# PandMshem.net
KiCad netlist of a schematic drawn in Altium Designer
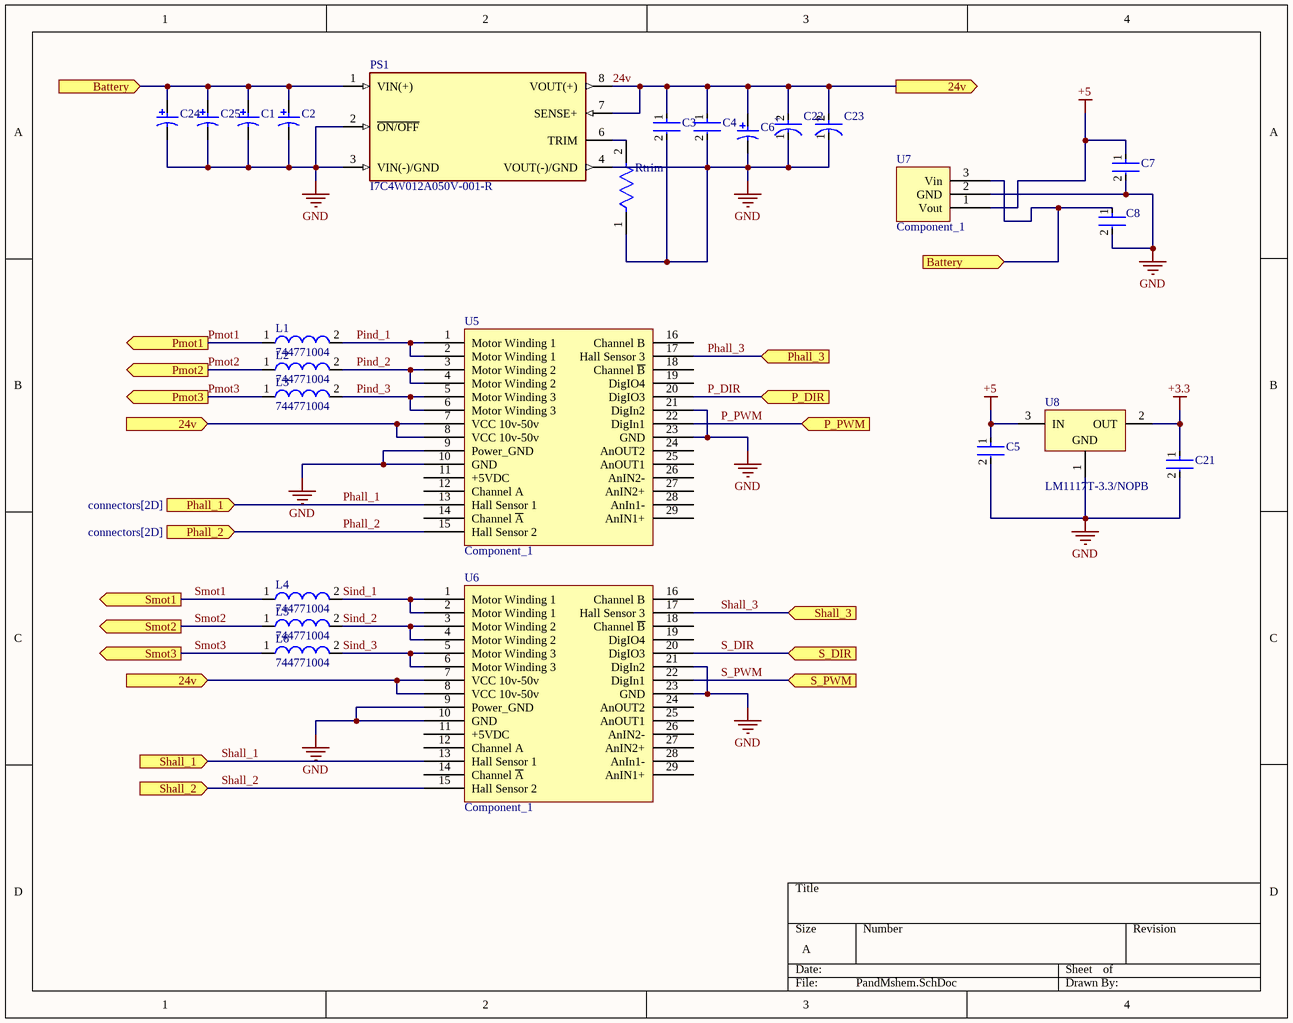
[diagram p0: PandMshem.SchDoc]

(export (version "E")
  (design (tool "Eeschema 10.0.6"))
  (components
    (comp (ref "C1")
      (value "ECA1HM101")
      (footprint "CAPPR65-350-1150X800X1250")
      (description "Aluminum Electrolytic Capacitor, 100 uF, +/- 20%, 50 V, -40 to 85 degC, 2-Pin THD, RoHS, Bulk")
      (fields (field (name "MANUFACTURER") "Panasonic") (field (name "VOLTAGE") "50V"))
      (libsource (lib "Altium Content Vault") (part "CAP-P-2"))
    )
    (comp (ref "C2")
      (value "ECA1HM220")
      (footprint "CAPPR55-200-1100X500X1200")
      (description "Aluminum Electrolytic Capacitor, 22 uF, +/- 20%, 50 V, -40 to 85 degC, 2-Pin THD, RoHS, Bulk")
      (fields (field (name "VOLTAGE") "50V") (field (name "MANUFACTURER") "Panasonic"))
      (libsource (lib "Altium Content Vault") (part "CAP-P-2"))
    )
    (comp (ref "C3")
      (value "08055C105KAT2A")
      (footprint "FP-0805-L_2_01_0_2-W_1_25-MFG")
      (description "General Purpose Ceramic Capacitor, 0805, 1uF, 10%, X7R, 15%, 50V")
      (fields (field (name "TOLERANCE") "10%") (field (name "VOLTAGE") "50V"))
      (libsource (lib "Altium Content Vault") (part "b4654b650e69147ec39a6b967a45e02"))
    )
    (comp (ref "C4")
      (value "C3225X7S1H106M250AB")
      (footprint "FP-C3225-250-0_4-IPC_C")
      (description "Multilayer Ceramic Capacitors 10uF ±20% 50V X7S SMD 1210")
      (fields (field (name "VOLTAGE") "50V") (field (name "TOLERANCE") "20%"))
      (libsource (lib "Altium Content Vault") (part "02cd4be3c70576c341d710602a673aa"))
    )
    (comp (ref "C5")
      (value "C3225X7S1H106M250AB")
      (footprint "FP-C3225-250-0_4-IPC_C")
      (description "Multilayer Ceramic Capacitors 10uF ±20% 50V X7S SMD 1210")
      (fields (field (name "VOLTAGE") "50V") (field (name "TOLERANCE") "20%"))
      (libsource (lib "Altium Content Vault") (part "02cd4be3c70576c341d710602a673aa"))
    )
    (comp (ref "C6")
      (value "ECA1HM101")
      (footprint "CAPPR65-350-1150X800X1250")
      (description "Aluminum Electrolytic Capacitor, 100 uF, +/- 20%, 50 V, -40 to 85 degC, 2-Pin THD, RoHS, Bulk")
      (fields (field (name "MANUFACTURER") "Panasonic") (field (name "VOLTAGE") "50V"))
      (libsource (lib "Altium Content Vault") (part "CAP-P-2"))
    )
    (comp (ref "C7")
      (value "GRM21BR61E226ME44L")
      (footprint "FP-GRM21B-0_2-e0_2_0_7-IPC_B")
      (description "Chip Multilayer Ceramic Capacitors for General Purpose, 0805, 22uF, X5R, 15%, 20%, 25V")
      (fields (field (name "TOLERANCE") "20%") (field (name "VOLTAGE") "25V"))
      (libsource (lib "Altium Content Vault") (part "b4654b650e69147ec39a6b967a45e02"))
    )
    (comp (ref "C8")
      (value "C3225X7S1H106M250AB")
      (footprint "FP-C3225-250-0_4-IPC_C")
      (description "Multilayer Ceramic Capacitors 10uF ±20% 50V X7S SMD 1210")
      (fields (field (name "VOLTAGE") "50V") (field (name "TOLERANCE") "20%"))
      (libsource (lib "Altium Content Vault") (part "02cd4be3c70576c341d710602a673aa"))
    )
    (comp (ref "C21")
      (value "GRM21BR61E226ME44L")
      (footprint "FP-GRM21B-0_2-e0_2_0_7-IPC_B")
      (description "Chip Multilayer Ceramic Capacitors for General Purpose, 0805, 22uF, X5R, 15%, 20%, 25V")
      (fields (field (name "TOLERANCE") "20%") (field (name "VOLTAGE") "25V"))
      (libsource (lib "Altium Content Vault") (part "b4654b650e69147ec39a6b967a45e02"))
    )
    (comp (ref "C22")
      (value "EEUFM1V331B")
      (footprint "FP-RAD-TH-D_10_0_5-L_16_1-MFG")
      (description "Aluminum Electrolytic Capacitors (Radial Lead Type) 330uF ±20% 35V")
      (fields (field (name "TOLERANCE") "20%"))
      (libsource (lib "Altium Content Vault") (part "a00bbbee19879c290e62620ae7e47b1"))
    )
    (comp (ref "C23")
      (value "EEUFM1V331B")
      (footprint "FP-RAD-TH-D_10_0_5-L_16_1-MFG")
      (description "Aluminum Electrolytic Capacitors (Radial Lead Type) 330uF ±20% 35V")
      (fields (field (name "TOLERANCE") "20%"))
      (libsource (lib "Altium Content Vault") (part "a00bbbee19879c290e62620ae7e47b1"))
    )
    (comp (ref "C24")
      (value "ECA1HM101")
      (footprint "CAPPR65-350-1150X800X1250")
      (description "Aluminum Electrolytic Capacitor, 100 uF, +/- 20%, 50 V, -40 to 85 degC, 2-Pin THD, RoHS, Bulk")
      (fields (field (name "MANUFACTURER") "Panasonic") (field (name "VOLTAGE") "50V"))
      (libsource (lib "Altium Content Vault") (part "CAP-P-2"))
    )
    (comp (ref "C25")
      (value "ECA1HM101")
      (footprint "CAPPR65-350-1150X800X1250")
      (description "Aluminum Electrolytic Capacitor, 100 uF, +/- 20%, 50 V, -40 to 85 degC, 2-Pin THD, RoHS, Bulk")
      (fields (field (name "MANUFACTURER") "Panasonic") (field (name "VOLTAGE") "50V"))
      (libsource (lib "Altium Content Vault") (part "CAP-P-2"))
    )
    (comp (ref "L1")
      (value "744771004")
      (footprint "WE-PD-L")
      (description "SMD-Shielded Power Inductor WE-PD, L = 4.70 µH")
      (libsource (lib "Altium Content Vault") (part "PAS-IND-INDUCTOR-2"))
    )
    (comp (ref "L2")
      (value "744771004")
      (footprint "WE-PD-L")
      (description "SMD-Shielded Power Inductor WE-PD, L = 4.70 µH")
      (libsource (lib "Altium Content Vault") (part "PAS-IND-INDUCTOR-2"))
    )
    (comp (ref "L3")
      (value "744771004")
      (footprint "WE-PD-L")
      (description "SMD-Shielded Power Inductor WE-PD, L = 4.70 µH")
      (libsource (lib "Altium Content Vault") (part "PAS-IND-INDUCTOR-2"))
    )
    (comp (ref "L4")
      (value "744771004")
      (footprint "WE-PD-L")
      (description "SMD-Shielded Power Inductor WE-PD, L = 4.70 µH")
      (libsource (lib "Altium Content Vault") (part "PAS-IND-INDUCTOR-2"))
    )
    (comp (ref "L5")
      (value "744771004")
      (footprint "WE-PD-L")
      (description "SMD-Shielded Power Inductor WE-PD, L = 4.70 µH")
      (libsource (lib "Altium Content Vault") (part "PAS-IND-INDUCTOR-2"))
    )
    (comp (ref "L6")
      (value "744771004")
      (footprint "WE-PD-L")
      (description "SMD-Shielded Power Inductor WE-PD, L = 4.70 µH")
      (libsource (lib "Altium Content Vault") (part "PAS-IND-INDUCTOR-2"))
    )
    (comp (ref "PS1")
      (value "I7C4W012A050V-001-R")
      (footprint "CONV_I7C4W012A050V-001-R")
      (description "Non-Isolated PoL Module DC DC Converter 1 Output 5 ~ 28V - - - 12.5A 9V - 53V Input")
      (fields (field (name "MF") "TDK-Lambda Americas Inc"))
      (libsource (lib "I7C4W012A050V-001-R") (part "I7C4W012A050V-001-R"))
    )
    (comp (ref "Rtrim")
      (value "CRCW0805560KFKEA")
      (footprint "FP-CRCW0805-e3-IPC_A")
      (description "RES Thick Film, 560kΩ, 1%, 0.125W, 100ppm/°C, 0805")
      (fields (field (name "TOLERANCE") "1%"))
      (libsource (lib "Altium Content Vault") (part "1029c3af85768c4190bb7ad29bc67b5"))
    )
    (comp (ref "U5")
      (value "Component_1")
      (footprint "Motor_Driver")
      (libsource (lib "MotorDriverSchem") (part "Component_1"))
    )
    (comp (ref "U6")
      (value "Component_1")
      (footprint "Motor_Driver")
      (libsource (lib "MotorDriverSchem") (part "Component_1"))
    )
    (comp (ref "U7")
      (value "Component_1")
      (footprint "5v_supply")
      (libsource (lib "5v_supply_Schem") (part "Component_1"))
    )
    (comp (ref "U8")
      (value "LM1117T-3.3/NOPB")
      (footprint "NDE0003A")
      (description "800mA Low-Dropout Linear Regulator, 3-pin TO-220, Pb-Free")
      (fields (field (name "MANUFACTURER") "Texas Instruments"))
      (libsource (lib "Altium Content Vault") (part "PM-REG-LM1086-SIL3"))
    )
  )
  (nets
    (net (code "1") (name "+3.3") (class "Default")
      (node (ref "C21") (pin "1") (pinfunction "1_1") (pintype "passive"))
      (node (ref "U8") (pin "2") (pinfunction "OUT_2") (pintype "power_in"))
    )
    (net (code "2") (name "+5") (class "Default")
      (node (ref "C5") (pin "1") (pinfunction "1_1") (pintype "passive"))
      (node (ref "C7") (pin "1") (pinfunction "1_1") (pintype "passive"))
      (node (ref "U7") (pin "1") (pinfunction "Vout_1") (pintype "passive"))
      (node (ref "U8") (pin "3") (pinfunction "IN_3") (pintype "power_in"))
    )
    (net (code "3") (name "/24v") (class "Default")
      (node (ref "C22") (pin "2") (pinfunction "A_2") (pintype "passive"))
      (node (ref "C23") (pin "2") (pinfunction "A_2") (pintype "passive"))
      (node (ref "C3") (pin "1") (pinfunction "1_1") (pintype "passive"))
      (node (ref "C4") (pin "1") (pinfunction "1_1") (pintype "passive"))
      (node (ref "C6") (pin "1") (pinfunction "1_1") (pintype "passive"))
      (node (ref "PS1") (pin "7") (pinfunction "SENSE+_7") (pintype "input"))
      (node (ref "PS1") (pin "8") (pinfunction "VOUT(+)_8") (pintype "output"))
      (node (ref "U5") (pin "7") (pinfunction "VCC_10v-50v_7") (pintype "passive"))
      (node (ref "U5") (pin "8") (pinfunction "VCC_10v-50v_8") (pintype "passive"))
      (node (ref "U6") (pin "7") (pinfunction "VCC_10v-50v_7") (pintype "passive"))
      (node (ref "U6") (pin "8") (pinfunction "VCC_10v-50v_8") (pintype "passive"))
    )
    (net (code "4") (name "/Battery") (class "Default")
      (node (ref "C1") (pin "1") (pinfunction "1_1") (pintype "passive"))
      (node (ref "C2") (pin "1") (pinfunction "1_1") (pintype "passive"))
      (node (ref "C24") (pin "1") (pinfunction "1_1") (pintype "passive"))
      (node (ref "C25") (pin "1") (pinfunction "1_1") (pintype "passive"))
      (node (ref "C8") (pin "1") (pinfunction "1_1") (pintype "passive"))
      (node (ref "PS1") (pin "1") (pinfunction "VIN(+)_1") (pintype "input"))
      (node (ref "U7") (pin "3") (pinfunction "Vin_3") (pintype "passive"))
    )
    (net (code "5") (name "/P_DIR") (class "Default")
      (node (ref "U5") (pin "20") (pinfunction "DigIO3_20") (pintype "passive"))
    )
    (net (code "6") (name "/P_PWM") (class "Default")
      (node (ref "U5") (pin "22") (pinfunction "DigIn1_22") (pintype "passive"))
    )
    (net (code "7") (name "/Phall_1") (class "Default")
      (node (ref "U5") (pin "13") (pinfunction "Hall_Sensor_1_13") (pintype "passive"))
    )
    (net (code "8") (name "/Phall_2") (class "Default")
      (node (ref "U5") (pin "15") (pinfunction "Hall_Sensor_2_15") (pintype "passive"))
    )
    (net (code "9") (name "/Phall_3") (class "Default")
      (node (ref "U5") (pin "17") (pinfunction "Hall_Sensor_3_17") (pintype "passive"))
    )
    (net (code "10") (name "/Pind_1") (class "Default")
      (node (ref "L1") (pin "2") (pinfunction "2_2") (pintype "passive"))
      (node (ref "U5") (pin "1") (pinfunction "Motor_Winding_1_1") (pintype "passive"))
      (node (ref "U5") (pin "2") (pinfunction "Motor_Winding_1_2") (pintype "passive"))
    )
    (net (code "11") (name "/Pind_2") (class "Default")
      (node (ref "L2") (pin "2") (pinfunction "2_2") (pintype "passive"))
      (node (ref "U5") (pin "3") (pinfunction "Motor_Winding_2_3") (pintype "passive"))
      (node (ref "U5") (pin "4") (pinfunction "Motor_Winding_2_4") (pintype "passive"))
    )
    (net (code "12") (name "/Pind_3") (class "Default")
      (node (ref "L3") (pin "2") (pinfunction "2_2") (pintype "passive"))
      (node (ref "U5") (pin "5") (pinfunction "Motor_Winding_3_5") (pintype "passive"))
      (node (ref "U5") (pin "6") (pinfunction "Motor_Winding_3_6") (pintype "passive"))
    )
    (net (code "13") (name "/Pmot1") (class "Default")
      (node (ref "L1") (pin "1") (pinfunction "1_1") (pintype "passive"))
    )
    (net (code "14") (name "/Pmot2") (class "Default")
      (node (ref "L2") (pin "1") (pinfunction "1_1") (pintype "passive"))
    )
    (net (code "15") (name "/Pmot3") (class "Default")
      (node (ref "L3") (pin "1") (pinfunction "1_1") (pintype "passive"))
    )
    (net (code "16") (name "/S_DIR") (class "Default")
      (node (ref "U6") (pin "20") (pinfunction "DigIO3_20") (pintype "passive"))
    )
    (net (code "17") (name "/S_PWM") (class "Default")
      (node (ref "U6") (pin "22") (pinfunction "DigIn1_22") (pintype "passive"))
    )
    (net (code "18") (name "/Shall_1") (class "Default")
      (node (ref "U6") (pin "13") (pinfunction "Hall_Sensor_1_13") (pintype "passive"))
    )
    (net (code "19") (name "/Shall_2") (class "Default")
      (node (ref "U6") (pin "15") (pinfunction "Hall_Sensor_2_15") (pintype "passive"))
    )
    (net (code "20") (name "/Shall_3") (class "Default")
      (node (ref "U6") (pin "17") (pinfunction "Hall_Sensor_3_17") (pintype "passive"))
    )
    (net (code "21") (name "/Sind_1") (class "Default")
      (node (ref "L4") (pin "2") (pinfunction "2_2") (pintype "passive"))
      (node (ref "U6") (pin "1") (pinfunction "Motor_Winding_1_1") (pintype "passive"))
      (node (ref "U6") (pin "2") (pinfunction "Motor_Winding_1_2") (pintype "passive"))
    )
    (net (code "22") (name "/Sind_2") (class "Default")
      (node (ref "L5") (pin "2") (pinfunction "2_2") (pintype "passive"))
      (node (ref "U6") (pin "3") (pinfunction "Motor_Winding_2_3") (pintype "passive"))
      (node (ref "U6") (pin "4") (pinfunction "Motor_Winding_2_4") (pintype "passive"))
    )
    (net (code "23") (name "/Sind_3") (class "Default")
      (node (ref "L6") (pin "2") (pinfunction "2_2") (pintype "passive"))
      (node (ref "U6") (pin "5") (pinfunction "Motor_Winding_3_5") (pintype "passive"))
      (node (ref "U6") (pin "6") (pinfunction "Motor_Winding_3_6") (pintype "passive"))
    )
    (net (code "24") (name "/Smot1") (class "Default")
      (node (ref "L4") (pin "1") (pinfunction "1_1") (pintype "passive"))
    )
    (net (code "25") (name "/Smot2") (class "Default")
      (node (ref "L5") (pin "1") (pinfunction "1_1") (pintype "passive"))
    )
    (net (code "26") (name "/Smot3") (class "Default")
      (node (ref "L6") (pin "1") (pinfunction "1_1") (pintype "passive"))
    )
    (net (code "27") (name "GND") (class "Default")
      (node (ref "C1") (pin "2") (pinfunction "2_2") (pintype "passive"))
      (node (ref "C2") (pin "2") (pinfunction "2_2") (pintype "passive"))
      (node (ref "C21") (pin "2") (pinfunction "2_2") (pintype "passive"))
      (node (ref "C22") (pin "1") (pinfunction "C_1") (pintype "passive"))
      (node (ref "C23") (pin "1") (pinfunction "C_1") (pintype "passive"))
      (node (ref "C24") (pin "2") (pinfunction "2_2") (pintype "passive"))
      (node (ref "C25") (pin "2") (pinfunction "2_2") (pintype "passive"))
      (node (ref "C3") (pin "2") (pinfunction "2_2") (pintype "passive"))
      (node (ref "C4") (pin "2") (pinfunction "2_2") (pintype "passive"))
      (node (ref "C5") (pin "2") (pinfunction "2_2") (pintype "passive"))
      (node (ref "C6") (pin "2") (pinfunction "2_2") (pintype "passive"))
      (node (ref "C7") (pin "2") (pinfunction "2_2") (pintype "passive"))
      (node (ref "C8") (pin "2") (pinfunction "2_2") (pintype "passive"))
      (node (ref "PS1") (pin "2") (pinfunction "~{ON/OFF}_2") (pintype "input"))
      (node (ref "PS1") (pin "3") (pinfunction "VIN(-)/GND_3") (pintype "input"))
      (node (ref "PS1") (pin "4") (pinfunction "VOUT(-)/GND_4") (pintype "output"))
      (node (ref "Rtrim") (pin "1") (pinfunction "1_1") (pintype "passive"))
      (node (ref "U5") (pin "10") (pinfunction "GND_10") (pintype "passive"))
      (node (ref "U5") (pin "21") (pinfunction "DigIn2_21") (pintype "passive"))
      (node (ref "U5") (pin "23") (pinfunction "GND_23") (pintype "passive"))
      (node (ref "U5") (pin "9") (pinfunction "Power_GND_9") (pintype "passive"))
      (node (ref "U6") (pin "10") (pinfunction "GND_10") (pintype "passive"))
      (node (ref "U6") (pin "21") (pinfunction "DigIn2_21") (pintype "passive"))
      (node (ref "U6") (pin "23") (pinfunction "GND_23") (pintype "passive"))
      (node (ref "U6") (pin "9") (pinfunction "Power_GND_9") (pintype "passive"))
      (node (ref "U7") (pin "2") (pinfunction "GND_2") (pintype "passive"))
      (node (ref "U8") (pin "1") (pinfunction "GND_1") (pintype "power_in"))
    )
    (net (code "28") (name "Net-(PS1-TRIM)") (class "Default")
      (node (ref "PS1") (pin "6") (pinfunction "TRIM_6") (pintype "passive"))
      (node (ref "Rtrim") (pin "2") (pinfunction "2_2") (pintype "passive"))
    )
    (net (code "29") (name "unconnected-(U5-+5VDC-Pad11)") (class "Default")
      (node (ref "U5") (pin "11") (pinfunction "+5VDC_11") (pintype "passive"))
    )
    (net (code "30") (name "unconnected-(U5-AnIN1+-Pad29)") (class "Default")
      (node (ref "U5") (pin "29") (pinfunction "AnIN1+_29") (pintype "passive"))
    )
    (net (code "31") (name "unconnected-(U5-AnIN2+-Pad27)") (class "Default")
      (node (ref "U5") (pin "27") (pinfunction "AnIN2+_27") (pintype "passive"))
    )
    (net (code "32") (name "unconnected-(U5-AnIN2--Pad26)") (class "Default")
      (node (ref "U5") (pin "26") (pinfunction "AnIN2-_26") (pintype "passive"))
    )
    (net (code "33") (name "unconnected-(U5-AnIn1--Pad28)") (class "Default")
      (node (ref "U5") (pin "28") (pinfunction "AnIn1-_28") (pintype "passive"))
    )
    (net (code "34") (name "unconnected-(U5-AnOUT1-Pad25)") (class "Default")
      (node (ref "U5") (pin "25") (pinfunction "AnOUT1_25") (pintype "passive"))
    )
    (net (code "35") (name "unconnected-(U5-AnOUT2-Pad24)") (class "Default")
      (node (ref "U5") (pin "24") (pinfunction "AnOUT2_24") (pintype "passive"))
    )
    (net (code "36") (name "unconnected-(U5-Channel_A-Pad12)") (class "Default")
      (node (ref "U5") (pin "12") (pinfunction "Channel_A_12") (pintype "passive"))
    )
    (net (code "37") (name "unconnected-(U5-Channel_B-Pad16)") (class "Default")
      (node (ref "U5") (pin "16") (pinfunction "Channel_B_16") (pintype "passive"))
    )
    (net (code "38") (name "unconnected-(U5-Channel_~{A}-Pad14)") (class "Default")
      (node (ref "U5") (pin "14") (pinfunction "Channel_~{A}_14") (pintype "passive"))
    )
    (net (code "39") (name "unconnected-(U5-Channel_~{B}-Pad18)") (class "Default")
      (node (ref "U5") (pin "18") (pinfunction "Channel_~{B}_18") (pintype "passive"))
    )
    (net (code "40") (name "unconnected-(U5-DigIO4-Pad19)") (class "Default")
      (node (ref "U5") (pin "19") (pinfunction "DigIO4_19") (pintype "passive"))
    )
    (net (code "41") (name "unconnected-(U6-+5VDC-Pad11)") (class "Default")
      (node (ref "U6") (pin "11") (pinfunction "+5VDC_11") (pintype "passive"))
    )
    (net (code "42") (name "unconnected-(U6-AnIN1+-Pad29)") (class "Default")
      (node (ref "U6") (pin "29") (pinfunction "AnIN1+_29") (pintype "passive"))
    )
    (net (code "43") (name "unconnected-(U6-AnIN2+-Pad27)") (class "Default")
      (node (ref "U6") (pin "27") (pinfunction "AnIN2+_27") (pintype "passive"))
    )
    (net (code "44") (name "unconnected-(U6-AnIN2--Pad26)") (class "Default")
      (node (ref "U6") (pin "26") (pinfunction "AnIN2-_26") (pintype "passive"))
    )
    (net (code "45") (name "unconnected-(U6-AnIn1--Pad28)") (class "Default")
      (node (ref "U6") (pin "28") (pinfunction "AnIn1-_28") (pintype "passive"))
    )
    (net (code "46") (name "unconnected-(U6-AnOUT1-Pad25)") (class "Default")
      (node (ref "U6") (pin "25") (pinfunction "AnOUT1_25") (pintype "passive"))
    )
    (net (code "47") (name "unconnected-(U6-AnOUT2-Pad24)") (class "Default")
      (node (ref "U6") (pin "24") (pinfunction "AnOUT2_24") (pintype "passive"))
    )
    (net (code "48") (name "unconnected-(U6-Channel_A-Pad12)") (class "Default")
      (node (ref "U6") (pin "12") (pinfunction "Channel_A_12") (pintype "passive"))
    )
    (net (code "49") (name "unconnected-(U6-Channel_B-Pad16)") (class "Default")
      (node (ref "U6") (pin "16") (pinfunction "Channel_B_16") (pintype "passive"))
    )
    (net (code "50") (name "unconnected-(U6-Channel_~{A}-Pad14)") (class "Default")
      (node (ref "U6") (pin "14") (pinfunction "Channel_~{A}_14") (pintype "passive"))
    )
    (net (code "51") (name "unconnected-(U6-Channel_~{B}-Pad18)") (class "Default")
      (node (ref "U6") (pin "18") (pinfunction "Channel_~{B}_18") (pintype "passive"))
    )
    (net (code "52") (name "unconnected-(U6-DigIO4-Pad19)") (class "Default")
      (node (ref "U6") (pin "19") (pinfunction "DigIO4_19") (pintype "passive"))
    )
  )
)
